# PR9028.net
KiCad netlist of a schematic drawn in EAGLE
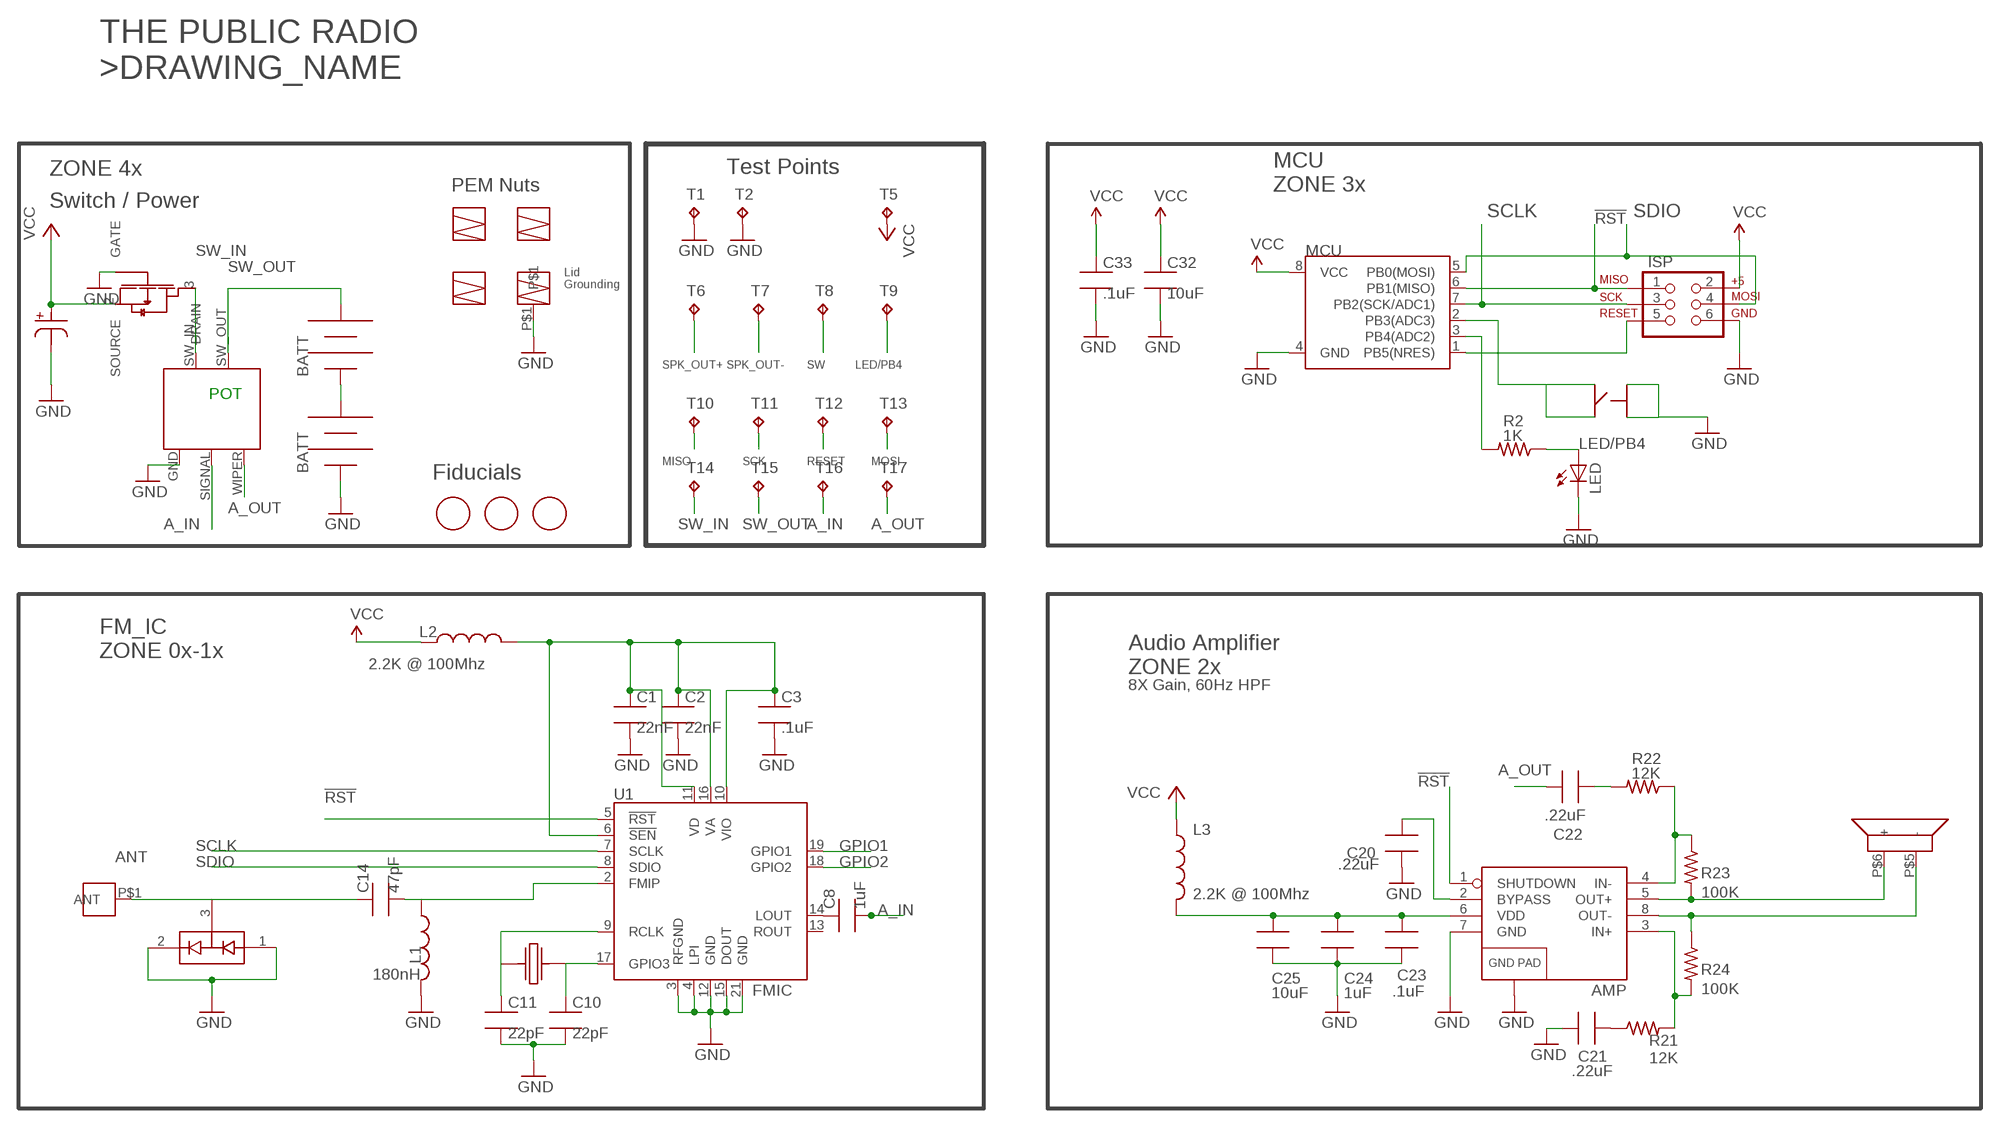
[diagram p0: schematic, sheet 1]

(export (version "E")
  (design (tool "Eeschema 10.0.6"))
  (components
    (comp (ref "AMP")
      (value "TPA6203A1")
      (footprint "eagle-import:8-MSOP")
      (libsource (lib "eagle-import") (part "TPA6203A1"))
    )
    (comp (ref "ANT_MOUNT")
      (value "PEM_M3_ANTENNA")
      (footprint "eagle-import:PEM_M3_ANTENNA")
      (libsource (lib "eagle-import") (part "PEM_M3_ANTENNA"))
    )
    (comp (ref "C1")
      (value "22nF")
      (footprint "eagle-import:0603_CPL")
      (fields
        (field (name "MFG_PN") "CL10B223KB8NNNC")
        (field (name "TOL") "10%")
        (field (name "VOLTAGE") "16V")
      )
      (libsource (lib "eagle-import") (part "C_SMT_0603_CPL"))
    )
    (comp (ref "C2")
      (value "22nF")
      (footprint "eagle-import:0603_CPL")
      (fields
        (field (name "MFG_PN") "CL10B223KB8NNNC")
        (field (name "TOL") "10%")
        (field (name "VOLTAGE") "16V")
      )
      (libsource (lib "eagle-import") (part "C_SMT_0603_CPL"))
    )
    (comp (ref "C3")
      (value ".1uF")
      (footprint "eagle-import:0603_CPL")
      (fields
        (field (name "MFG_PN") "CL10B104KB8SFNC")
        (field (name "TOL") "10%")
        (field (name "VOLTAGE") "16V")
      )
      (libsource (lib "eagle-import") (part "C_SMT_0603_CPL"))
    )
    (comp (ref "C8")
      (value "1uF")
      (footprint "eagle-import:0603_CPL")
      (fields
        (field (name "MFG_PN") "CL10B105KP8NNNC")
        (field (name "TOL") "10%")
        (field (name "VOLTAGE") "10V")
      )
      (libsource (lib "eagle-import") (part "C_SMT_0603_CPL"))
    )
    (comp (ref "C10")
      (value "22pF")
      (footprint "eagle-import:0603_CPL")
      (fields
        (field (name "MFG_PN") "C1608C0G1H220J080AA")
        (field (name "TOL") "5%")
        (field (name "VOLTAGE") "50V")
      )
      (libsource (lib "eagle-import") (part "C_SMT_0603_CPL"))
    )
    (comp (ref "C11")
      (value "22pF")
      (footprint "eagle-import:0603_CPL")
      (fields
        (field (name "MFG_PN") "C1608C0G1H220J080AA")
        (field (name "TOL") "5%")
        (field (name "VOLTAGE") "50V")
      )
      (libsource (lib "eagle-import") (part "C_SMT_0603_CPL"))
    )
    (comp (ref "C14")
      (value "47pF")
      (footprint "eagle-import:0603_CPL")
      (fields
        (field (name "MFG_PN") "CL10C470JB8NCNC")
        (field (name "TOL") "5%")
        (field (name "VOLTAGE") "50V")
      )
      (libsource (lib "eagle-import") (part "C_SMT_0603_CPL"))
    )
    (comp (ref "C20")
      (value ".22uF")
      (footprint "eagle-import:0603_CPL")
      (fields
        (field (name "MFG_PN") "C1608X7R1C224K080AC")
        (field (name "TOL") "10%")
        (field (name "VOLTAGE") "16V")
      )
      (libsource (lib "eagle-import") (part "C_SMT_0603_CPL"))
    )
    (comp (ref "C21")
      (value ".22uF")
      (footprint "eagle-import:0603_CPL")
      (fields
        (field (name "MFG_PN") "C1608X7R1C224K080AC")
        (field (name "TOL") "10%")
        (field (name "VOLTAGE") "16V")
      )
      (libsource (lib "eagle-import") (part "C_SMT_0603_CPL"))
    )
    (comp (ref "C22")
      (value ".22uF")
      (footprint "eagle-import:0603_CPL")
      (fields
        (field (name "MFG_PN") "C1608X7R1C224K080AC")
        (field (name "TOL") "10%")
        (field (name "VOLTAGE") "16V")
      )
      (libsource (lib "eagle-import") (part "C_SMT_0603_CPL"))
    )
    (comp (ref "C23")
      (value ".1uF")
      (footprint "eagle-import:0603_CPL")
      (fields
        (field (name "MFG_PN") "CL10B104KB8SFNC")
        (field (name "TOL") "10%")
        (field (name "VOLTAGE") "16V")
      )
      (libsource (lib "eagle-import") (part "C_SMT_0603_CPL"))
    )
    (comp (ref "C24")
      (value "1uF")
      (footprint "eagle-import:0603_CPL")
      (fields
        (field (name "MFG_PN") "CL10B105KP8NNNC")
        (field (name "TOL") "10%")
        (field (name "VOLTAGE") "10V")
      )
      (libsource (lib "eagle-import") (part "C_SMT_0603_CPL"))
    )
    (comp (ref "C25")
      (value "10uF")
      (footprint "eagle-import:0603_CPL")
      (fields
        (field (name "MFG_PN") "CL10A106MQ8NNNC")
        (field (name "TOL") "20%")
        (field (name "VOLTAGE") "6.3V")
      )
      (libsource (lib "eagle-import") (part "C_SMT_0603_CPL"))
    )
    (comp (ref "C32")
      (value "10uF")
      (footprint "eagle-import:0603_CPL")
      (fields
        (field (name "MFG_PN") "CL10A106MQ8NNNC")
        (field (name "TOL") "20%")
        (field (name "VOLTAGE") "6.3V")
      )
      (libsource (lib "eagle-import") (part "C_SMT_0603_CPL"))
    )
    (comp (ref "C33")
      (value ".1uF")
      (footprint "eagle-import:0603_CPL")
      (fields
        (field (name "MFG_PN") "CL10B104KB8SFNC")
        (field (name "TOL") "10%")
        (field (name "VOLTAGE") "16V")
      )
      (libsource (lib "eagle-import") (part "C_SMT_0603_CPL"))
    )
    (comp (ref "C40")
      (value "220uF")
      (footprint "eagle-import:NICHICON_UD_63")
      (fields (field (name "TOL") "20%") (field (name "VOLTAGE") "16V"))
      (libsource (lib "eagle-import") (part "NICHICON_SERIESUD"))
    )
    (comp (ref "D1")
      (value "BAV99")
      (footprint "eagle-import:SOT23_CPL")
      (fields (field (name "MFG_PN") "BAV99,215"))
      (libsource (lib "eagle-import") (part "BAV99"))
    )
    (comp (ref "FET1")
      (value "AO3435")
      (footprint "eagle-import:SOT23_CPL")
      (fields (field (name "MFG_PN") "AO3435"))
      (libsource (lib "eagle-import") (part "AO3435"))
    )
    (comp (ref "ISP")
      (value "AVR_SPI_PRG_6NS")
      (footprint "eagle-import:2X3-NS")
      (fields (field (name "MFG_PN") "DNP"))
      (libsource (lib "eagle-import") (part "AVR_SPI_PRG_6NS"))
    )
    (comp (ref "JP5")
      (value "BK-92_MPD_AA_BATT_CLIP")
      (footprint "eagle-import:BK92_AA_BATT")
      (fields (field (name "MFG_PN") "Consigned"))
      (libsource (lib "eagle-import") (part "BK-92_MPD_AA_BATT_CLIP"))
    )
    (comp (ref "JP6")
      (value "BK-92_MPD_AA_BATT_CLIP")
      (footprint "eagle-import:BK92_AA_BATT")
      (fields (field (name "MFG_PN") "Consigned"))
      (libsource (lib "eagle-import") (part "BK-92_MPD_AA_BATT_CLIP"))
    )
    (comp (ref "L1")
      (value "180nH")
      (footprint "eagle-import:0805_ADAFRUIT")
      (fields
        (field (name "CURRENT") "400mA")
        (field (name "DCR") "640m")
        (field (name "MFG_PN") "AISC-0805-R18J-T ")
        (field (name "TOL") "5%")
      )
      (libsource (lib "eagle-import") (part "L_SMT_0805_ADAFRUIT"))
    )
    (comp (ref "L2")
      (value "2.2K @ 100Mhz")
      (footprint "eagle-import:0603_CPL")
      (libsource (lib "eagle-import") (part "L_SMT_0603_CPL"))
    )
    (comp (ref "L3")
      (value "2.2K @ 100Mhz")
      (footprint "eagle-import:0603_CPL")
      (libsource (lib "eagle-import") (part "L_SMT_0603_CPL"))
    )
    (comp (ref "LED")
      (value "HSMC-C265_REVERSE_MOUNT_LED")
      (footprint "eagle-import:HSMA-C265_REVERSE_MOUN_LED")
      (libsource (lib "eagle-import") (part "HSMC-C265_REVERSE_MOUNT_LED"))
    )
    (comp (ref "MARK1")
      (value "FIDUCIAL")
      (footprint "eagle-import:FIDUCIAL_1MM")
      (libsource (lib "eagle-import") (part "FIDUCIAL"))
    )
    (comp (ref "MARK2")
      (value "FIDUCIAL")
      (footprint "eagle-import:FIDUCIAL_1MM")
      (libsource (lib "eagle-import") (part "FIDUCIAL"))
    )
    (comp (ref "MARK3")
      (value "FIDUCIAL")
      (footprint "eagle-import:FIDUCIAL_1MM")
      (libsource (lib "eagle-import") (part "FIDUCIAL"))
    )
    (comp (ref "MCU")
      (value "ATTINY45TINY45-20-SMT")
      (footprint "eagle-import:8-SOIC")
      (fields (field (name "MFG_PN") "ATTINY25-20SUR "))
      (libsource (lib "eagle-import") (part "ATTINY45TINY45-20-SMT"))
    )
    (comp (ref "R1")
      (value "VOLUME_POTTAIWAN_ALPHA")
      (footprint "eagle-import:RV170SF_SW_POT")
      (libsource (lib "eagle-import") (part "VOLUME_POTTAIWAN_ALPHA"))
    )
    (comp (ref "R2")
      (value "1K")
      (footprint "eagle-import:0603_CPL")
      (fields
        (field (name "MFG_PN") "RR0816P-102-D")
        (field (name "POWER") "1/10W")
        (field (name "TOL") "1%")
      )
      (libsource (lib "eagle-import") (part "R_SMT_R0603_CPL"))
    )
    (comp (ref "R21")
      (value "12K")
      (footprint "eagle-import:0603_CPL")
      (fields
        (field (name "MFG_PN") "RC0603FR-0712KL")
        (field (name "POWER") "1/10W")
        (field (name "TOL") "1%")
      )
      (libsource (lib "eagle-import") (part "R_SMT_R0603_CPL"))
    )
    (comp (ref "R22")
      (value "12K")
      (footprint "eagle-import:0603_CPL")
      (fields
        (field (name "MFG_PN") "RC0603FR-0712KL")
        (field (name "POWER") "1/10W")
        (field (name "TOL") "1%")
      )
      (libsource (lib "eagle-import") (part "R_SMT_R0603_CPL"))
    )
    (comp (ref "R23")
      (value "100K")
      (footprint "eagle-import:0603_CPL")
      (fields
        (field (name "MFG_PN") "ERJ-3EKF1003V")
        (field (name "POWER") "1/10W")
        (field (name "TOL") "1%")
      )
      (libsource (lib "eagle-import") (part "R_SMT_R0603_CPL"))
    )
    (comp (ref "R24")
      (value "100K")
      (footprint "eagle-import:0603_CPL")
      (fields
        (field (name "MFG_PN") "ERJ-3EKF1003V")
        (field (name "POWER") "1/10W")
        (field (name "TOL") "1%")
      )
      (libsource (lib "eagle-import") (part "R_SMT_R0603_CPL"))
    )
    (comp (ref "SPEAKER")
      (value "PR2023_GROUND_UP_SPEAKER")
      (footprint "eagle-import:PR2023_GROUND_UP_SPEAKER")
      (libsource (lib "eagle-import") (part "PR2023_GROUND_UP_SPEAKER"))
    )
    (comp (ref "SPEAKER_PEM_1")
      (value "PEM_M3_SPK")
      (footprint "eagle-import:PEM_M3_SPK")
      (libsource (lib "eagle-import") (part "PEM_M3_SPK"))
    )
    (comp (ref "SPEAKER_PEM_2")
      (value "PEM_M3_SPK")
      (footprint "eagle-import:PEM_M3_SPK")
      (libsource (lib "eagle-import") (part "PEM_M3_SPK"))
    )
    (comp (ref "SPEAKER_PEM_3")
      (value "PEM_M3_SPK_GROUND")
      (footprint "eagle-import:PEM_M3_SPK")
      (libsource (lib "eagle-import") (part "PEM_M3_SPK_GROUND"))
    )
    (comp (ref "SPEAKER_PEM_4")
      (value "PEM_M3_SPK")
      (footprint "eagle-import:PEM_M3_SPK")
      (libsource (lib "eagle-import") (part "PEM_M3_SPK"))
    )
    (comp (ref "SW1")
      (value "C&K_PTS645")
      (footprint "eagle-import:C&K_PTS645_SMT")
      (libsource (lib "eagle-import") (part "C&K_PTS645"))
    )
    (comp (ref "T1")
      (value "TPTP20R")
      (footprint "eagle-import:TP20R")
      (libsource (lib "eagle-import") (part "TPTP20R"))
    )
    (comp (ref "T2")
      (value "TPTP20R")
      (footprint "eagle-import:TP20R")
      (libsource (lib "eagle-import") (part "TPTP20R"))
    )
    (comp (ref "T5")
      (value "TPTP20R")
      (footprint "eagle-import:TP20R")
      (libsource (lib "eagle-import") (part "TPTP20R"))
    )
    (comp (ref "T6")
      (value "TPTP20R")
      (footprint "eagle-import:TP20R")
      (libsource (lib "eagle-import") (part "TPTP20R"))
    )
    (comp (ref "T7")
      (value "TPTP20R")
      (footprint "eagle-import:TP20R")
      (libsource (lib "eagle-import") (part "TPTP20R"))
    )
    (comp (ref "T8")
      (value "TPTP20R")
      (footprint "eagle-import:TP20R")
      (libsource (lib "eagle-import") (part "TPTP20R"))
    )
    (comp (ref "T9")
      (value "TPTP20R")
      (footprint "eagle-import:TP20R")
      (libsource (lib "eagle-import") (part "TPTP20R"))
    )
    (comp (ref "T10")
      (value "TPTP20R")
      (footprint "eagle-import:TP20R")
      (libsource (lib "eagle-import") (part "TPTP20R"))
    )
    (comp (ref "T11")
      (value "TPTP20R")
      (footprint "eagle-import:TP20R")
      (libsource (lib "eagle-import") (part "TPTP20R"))
    )
    (comp (ref "T12")
      (value "TPTP20R")
      (footprint "eagle-import:TP20R")
      (libsource (lib "eagle-import") (part "TPTP20R"))
    )
    (comp (ref "T13")
      (value "TPTP20R")
      (footprint "eagle-import:TP20R")
      (libsource (lib "eagle-import") (part "TPTP20R"))
    )
    (comp (ref "T14")
      (value "TPTP20R")
      (footprint "eagle-import:TP20R")
      (libsource (lib "eagle-import") (part "TPTP20R"))
    )
    (comp (ref "T15")
      (value "TPTP20R")
      (footprint "eagle-import:TP20R")
      (libsource (lib "eagle-import") (part "TPTP20R"))
    )
    (comp (ref "T16")
      (value "TPTP20R")
      (footprint "eagle-import:TP20R")
      (libsource (lib "eagle-import") (part "TPTP20R"))
    )
    (comp (ref "T17")
      (value "TPTP20R")
      (footprint "eagle-import:TP20R")
      (libsource (lib "eagle-import") (part "TPTP20R"))
    )
    (comp (ref "U1")
      (value "FMIC")
      (footprint "eagle-import:SI470X_20_QFN")
      (fields (field (name "MFG_PN") "SI4702-C19-GMR"))
      (libsource (lib "eagle-import") (part "SI4702-C19-GMR"))
    )
    (comp (ref "X1")
      (value "ABS25XTAL")
      (footprint "eagle-import:4-SOJ")
      (libsource (lib "eagle-import") (part "ABS25XTAL"))
    )
  )
  (nets
    (net (code "1") (name "/ANT") (class "Default")
      (node (ref "ANT_MOUNT") (pin "P$1") (pinfunction "ANT_P$1") (pintype "bidirectional"))
      (node (ref "C14") (pin "1") (pinfunction "1_1") (pintype "passive"))
      (node (ref "D1") (pin "3") (pinfunction "COM_3") (pintype "bidirectional"))
    )
    (net (code "2") (name "/A_IN") (class "Default")
      (node (ref "C8") (pin "2") (pinfunction "2_2") (pintype "passive"))
      (node (ref "R1") (pin "SIGNAL") (pinfunction "SIGNAL_SIGNAL") (pintype "bidirectional"))
      (node (ref "T16") (pin "TP") (pinfunction "TP_TP") (pintype "input"))
    )
    (net (code "3") (name "/A_OUT") (class "Default")
      (node (ref "C22") (pin "2") (pinfunction "2_2") (pintype "passive"))
      (node (ref "R1") (pin "WIPER") (pinfunction "WIPER_WIPER") (pintype "bidirectional"))
      (node (ref "T17") (pin "TP") (pinfunction "TP_TP") (pintype "input"))
    )
    (net (code "4") (name "/GPIO1") (class "Default")
      (node (ref "U1") (pin "19") (pinfunction "GPIO1_19") (pintype "bidirectional"))
    )
    (net (code "5") (name "/GPIO2") (class "Default")
      (node (ref "U1") (pin "18") (pinfunction "GPIO2_18") (pintype "bidirectional"))
    )
    (net (code "6") (name "/LED{slash}PB4") (class "Default")
      (node (ref "MCU") (pin "3") (pinfunction "PB4(ADC2)_3") (pintype "bidirectional"))
      (node (ref "R2") (pin "2") (pinfunction "2_2") (pintype "passive"))
      (node (ref "T9") (pin "TP") (pinfunction "TP_TP") (pintype "input"))
    )
    (net (code "7") (name "/RESET") (class "Default")
      (node (ref "ISP") (pin "5") (pinfunction "5_5") (pintype "passive"))
      (node (ref "MCU") (pin "1") (pinfunction "PB5(NRES)_1") (pintype "bidirectional"))
      (node (ref "T12") (pin "TP") (pinfunction "TP_TP") (pintype "input"))
    )
    (net (code "8") (name "/SCLK") (class "Default")
      (node (ref "ISP") (pin "3") (pinfunction "3_3") (pintype "passive"))
      (node (ref "MCU") (pin "7") (pinfunction "PB2(SCK/ADC1)_7") (pintype "bidirectional"))
      (node (ref "T11") (pin "TP") (pinfunction "TP_TP") (pintype "input"))
      (node (ref "U1") (pin "7") (pinfunction "SCLK_7") (pintype "bidirectional"))
    )
    (net (code "9") (name "/SDIO") (class "Default")
      (node (ref "ISP") (pin "4") (pinfunction "4_4") (pintype "passive"))
      (node (ref "MCU") (pin "5") (pinfunction "PB0(MOSI)_5") (pintype "bidirectional"))
      (node (ref "T13") (pin "TP") (pinfunction "TP_TP") (pintype "input"))
      (node (ref "U1") (pin "8") (pinfunction "SDIO_8") (pintype "bidirectional"))
    )
    (net (code "10") (name "/SPK_OUT+") (class "Default")
      (node (ref "AMP") (pin "5") (pinfunction "OUT+_5") (pintype "bidirectional"))
      (node (ref "R23") (pin "2") (pinfunction "2_2") (pintype "passive"))
      (node (ref "SPEAKER") (pin "P$6") (pinfunction "+_P$6") (pintype "bidirectional"))
      (node (ref "T6") (pin "TP") (pinfunction "TP_TP") (pintype "input"))
    )
    (net (code "11") (name "/SPK_OUT-") (class "Default")
      (node (ref "AMP") (pin "8") (pinfunction "OUT-_8") (pintype "bidirectional"))
      (node (ref "R24") (pin "1") (pinfunction "1_1") (pintype "passive"))
      (node (ref "SPEAKER") (pin "P$5") (pinfunction "-_P$5") (pintype "bidirectional"))
      (node (ref "T7") (pin "TP") (pinfunction "TP_TP") (pintype "input"))
    )
    (net (code "12") (name "/SW") (class "Default")
      (node (ref "MCU") (pin "2") (pinfunction "PB3(ADC3)_2") (pintype "bidirectional"))
      (node (ref "SW1") (pin "P$3") (pinfunction "P$3_P$3") (pintype "bidirectional"))
      (node (ref "SW1") (pin "P$4") (pinfunction "P$4_P$4") (pintype "bidirectional"))
      (node (ref "T8") (pin "TP") (pinfunction "TP_TP") (pintype "input"))
    )
    (net (code "13") (name "/SW_IN") (class "Default")
      (node (ref "FET1") (pin "3") (pinfunction "DRAIN_3") (pintype "bidirectional"))
      (node (ref "R1") (pin "SW_IN") (pinfunction "SW_IN_SW_IN") (pintype "bidirectional"))
      (node (ref "T14") (pin "TP") (pinfunction "TP_TP") (pintype "input"))
    )
    (net (code "14") (name "/SW_OUT") (class "Default")
      (node (ref "JP5") (pin "POS") (pinfunction "POS_POS") (pintype "bidirectional"))
      (node (ref "JP5") (pin "POS@2") (pinfunction "POS_POS@2") (pintype "bidirectional"))
      (node (ref "R1") (pin "SW_OUT") (pinfunction "SW_OUT_SW_OUT") (pintype "bidirectional"))
      (node (ref "T15") (pin "TP") (pinfunction "TP_TP") (pintype "input"))
    )
    (net (code "15") (name "/~{RST}") (class "Default")
      (node (ref "AMP") (pin "1") (pinfunction "SHUTDOWN_1") (pintype "input"))
      (node (ref "ISP") (pin "1") (pinfunction "1_1") (pintype "passive"))
      (node (ref "MCU") (pin "6") (pinfunction "PB1(MISO)_6") (pintype "bidirectional"))
      (node (ref "T10") (pin "TP") (pinfunction "TP_TP") (pintype "input"))
      (node (ref "U1") (pin "5") (pinfunction "~{RST}_5") (pintype "bidirectional"))
    )
    (net (code "16") (name "GND") (class "Default")
      (node (ref "AMP") (pin "7") (pinfunction "GND_7") (pintype "power_in"))
      (node (ref "AMP") (pin "9") (pinfunction "GND_9") (pintype "power_in"))
      (node (ref "C1") (pin "2") (pinfunction "2_2") (pintype "passive"))
      (node (ref "C10") (pin "2") (pinfunction "2_2") (pintype "passive"))
      (node (ref "C11") (pin "2") (pinfunction "2_2") (pintype "passive"))
      (node (ref "C2") (pin "2") (pinfunction "2_2") (pintype "passive"))
      (node (ref "C20") (pin "1") (pinfunction "1_1") (pintype "passive"))
      (node (ref "C21") (pin "1") (pinfunction "1_1") (pintype "passive"))
      (node (ref "C23") (pin "2") (pinfunction "2_2") (pintype "passive"))
      (node (ref "C24") (pin "2") (pinfunction "2_2") (pintype "passive"))
      (node (ref "C25") (pin "2") (pinfunction "2_2") (pintype "passive"))
      (node (ref "C3") (pin "2") (pinfunction "2_2") (pintype "passive"))
      (node (ref "C32") (pin "2") (pinfunction "2_2") (pintype "passive"))
      (node (ref "C33") (pin "2") (pinfunction "2_2") (pintype "passive"))
      (node (ref "C40") (pin "P$2") (pinfunction "P$2_P$2") (pintype "bidirectional"))
      (node (ref "D1") (pin "1") (pinfunction "A1_1") (pintype "bidirectional"))
      (node (ref "D1") (pin "2") (pinfunction "C2_2") (pintype "bidirectional"))
      (node (ref "FET1") (pin "1") (pinfunction "GATE_1") (pintype "bidirectional"))
      (node (ref "ISP") (pin "6") (pinfunction "6_6") (pintype "passive"))
      (node (ref "JP6") (pin "NEG") (pinfunction "NEG_NEG") (pintype "bidirectional"))
      (node (ref "JP6") (pin "NEG@2") (pinfunction "NEG_NEG@2") (pintype "bidirectional"))
      (node (ref "L1") (pin "2") (pinfunction "2_2") (pintype "passive"))
      (node (ref "LED") (pin "P$2") (pinfunction "GND_P$2") (pintype "passive"))
      (node (ref "MCU") (pin "4") (pinfunction "GND_4") (pintype "bidirectional"))
      (node (ref "R1") (pin "GND") (pinfunction "GND_GND") (pintype "bidirectional"))
      (node (ref "SPEAKER_PEM_3") (pin "P$1") (pinfunction "P$1_P$1") (pintype "bidirectional"))
      (node (ref "SW1") (pin "P$1") (pinfunction "P$1_P$1") (pintype "bidirectional"))
      (node (ref "SW1") (pin "P$2") (pinfunction "P$2_P$2") (pintype "bidirectional"))
      (node (ref "T1") (pin "TP") (pinfunction "TP_TP") (pintype "input"))
      (node (ref "T2") (pin "TP") (pinfunction "TP_TP") (pintype "input"))
      (node (ref "U1") (pin "12") (pinfunction "GND_12") (pintype "bidirectional"))
      (node (ref "U1") (pin "15") (pinfunction "DOUT_15") (pintype "bidirectional"))
      (node (ref "U1") (pin "21") (pinfunction "GND_21") (pintype "bidirectional"))
      (node (ref "U1") (pin "3") (pinfunction "RFGND_3") (pintype "bidirectional"))
      (node (ref "U1") (pin "4") (pinfunction "LPI_4") (pintype "bidirectional"))
    )
    (net (code "17") (name "Net-(AMP-BYPASS)") (class "Default")
      (node (ref "AMP") (pin "2") (pinfunction "BYPASS_2") (pintype "bidirectional"))
      (node (ref "C20") (pin "2") (pinfunction "2_2") (pintype "passive"))
    )
    (net (code "18") (name "Net-(AMP-IN+)") (class "Default")
      (node (ref "AMP") (pin "3") (pinfunction "IN+_3") (pintype "bidirectional"))
      (node (ref "R21") (pin "2") (pinfunction "2_2") (pintype "passive"))
      (node (ref "R24") (pin "2") (pinfunction "2_2") (pintype "passive"))
    )
    (net (code "19") (name "Net-(AMP-IN-)") (class "Default")
      (node (ref "AMP") (pin "4") (pinfunction "IN-_4") (pintype "bidirectional"))
      (node (ref "R22") (pin "1") (pinfunction "1_1") (pintype "passive"))
      (node (ref "R23") (pin "1") (pinfunction "1_1") (pintype "passive"))
    )
    (net (code "20") (name "Net-(AMP-VDD)") (class "Default")
      (node (ref "AMP") (pin "6") (pinfunction "VDD_6") (pintype "power_in"))
      (node (ref "C23") (pin "1") (pinfunction "1_1") (pintype "passive"))
      (node (ref "C24") (pin "1") (pinfunction "1_1") (pintype "passive"))
      (node (ref "C25") (pin "1") (pinfunction "1_1") (pintype "passive"))
      (node (ref "L3") (pin "2") (pinfunction "2_2") (pintype "passive"))
    )
    (net (code "21") (name "Net-(C21-Pad2)") (class "Default")
      (node (ref "C21") (pin "2") (pinfunction "2_2") (pintype "passive"))
      (node (ref "R21") (pin "1") (pinfunction "1_1") (pintype "passive"))
    )
    (net (code "22") (name "Net-(C22-Pad1)") (class "Default")
      (node (ref "C22") (pin "1") (pinfunction "1_1") (pintype "passive"))
      (node (ref "R22") (pin "2") (pinfunction "2_2") (pintype "passive"))
    )
    (net (code "23") (name "Net-(JP5-NEG-PadNEG@2)") (class "Default")
      (node (ref "JP5") (pin "NEG") (pinfunction "NEG_NEG") (pintype "bidirectional"))
      (node (ref "JP5") (pin "NEG@2") (pinfunction "NEG_NEG@2") (pintype "bidirectional"))
      (node (ref "JP6") (pin "POS") (pinfunction "POS_POS") (pintype "bidirectional"))
      (node (ref "JP6") (pin "POS@2") (pinfunction "POS_POS@2") (pintype "bidirectional"))
    )
    (net (code "24") (name "Net-(LED-VCC)") (class "Default")
      (node (ref "LED") (pin "P$1") (pinfunction "VCC_P$1") (pintype "passive"))
      (node (ref "R2") (pin "1") (pinfunction "1_1") (pintype "passive"))
    )
    (net (code "25") (name "Net-(U1-FMIP)") (class "Default")
      (node (ref "C14") (pin "2") (pinfunction "2_2") (pintype "passive"))
      (node (ref "L1") (pin "1") (pinfunction "1_1") (pintype "passive"))
      (node (ref "U1") (pin "2") (pinfunction "FMIP_2") (pintype "bidirectional"))
    )
    (net (code "26") (name "Net-(U1-GPIO3)") (class "Default")
      (node (ref "C10") (pin "1") (pinfunction "1_1") (pintype "passive"))
      (node (ref "U1") (pin "17") (pinfunction "GPIO3_17") (pintype "bidirectional"))
      (node (ref "X1") (pin "P$4") (pinfunction "P$4_P$4") (pintype "bidirectional"))
    )
    (net (code "27") (name "Net-(U1-LOUT)") (class "Default")
      (node (ref "C8") (pin "1") (pinfunction "1_1") (pintype "passive"))
      (node (ref "U1") (pin "14") (pinfunction "LOUT_14") (pintype "bidirectional"))
    )
    (net (code "28") (name "Net-(U1-RCLK)") (class "Default")
      (node (ref "C11") (pin "1") (pinfunction "1_1") (pintype "passive"))
      (node (ref "U1") (pin "9") (pinfunction "RCLK_9") (pintype "bidirectional"))
      (node (ref "X1") (pin "P$1") (pinfunction "P$1_P$1") (pintype "bidirectional"))
    )
    (net (code "29") (name "Net-(U1-VA)") (class "Default")
      (node (ref "C1") (pin "1") (pinfunction "1_1") (pintype "passive"))
      (node (ref "C2") (pin "1") (pinfunction "1_1") (pintype "passive"))
      (node (ref "C3") (pin "1") (pinfunction "1_1") (pintype "passive"))
      (node (ref "L2") (pin "2") (pinfunction "2_2") (pintype "passive"))
      (node (ref "U1") (pin "10") (pinfunction "VIO_10") (pintype "bidirectional"))
      (node (ref "U1") (pin "11") (pinfunction "VD_11") (pintype "bidirectional"))
      (node (ref "U1") (pin "16") (pinfunction "VA_16") (pintype "bidirectional"))
      (node (ref "U1") (pin "6") (pinfunction "~{SEN}_6") (pintype "bidirectional"))
    )
    (net (code "30") (name "VCC") (class "Default")
      (node (ref "C32") (pin "1") (pinfunction "1_1") (pintype "passive"))
      (node (ref "C33") (pin "1") (pinfunction "1_1") (pintype "passive"))
      (node (ref "C40") (pin "P$1") (pinfunction "P$1_P$1") (pintype "bidirectional"))
      (node (ref "FET1") (pin "2") (pinfunction "SOURCE_2") (pintype "bidirectional"))
      (node (ref "ISP") (pin "2") (pinfunction "2_2") (pintype "passive"))
      (node (ref "L2") (pin "1") (pinfunction "1_1") (pintype "passive"))
      (node (ref "L3") (pin "1") (pinfunction "1_1") (pintype "passive"))
      (node (ref "MCU") (pin "8") (pinfunction "VCC_8") (pintype "bidirectional"))
      (node (ref "T5") (pin "TP") (pinfunction "TP_TP") (pintype "input"))
    )
    (net (code "31") (name "unconnected-(U1-ROUT-Pad13)") (class "Default")
      (node (ref "U1") (pin "13") (pinfunction "ROUT_13") (pintype "bidirectional"))
    )
  )
)
